# USB_CP2104.net
KiCad netlist of a schematic drawn in Altium Designer
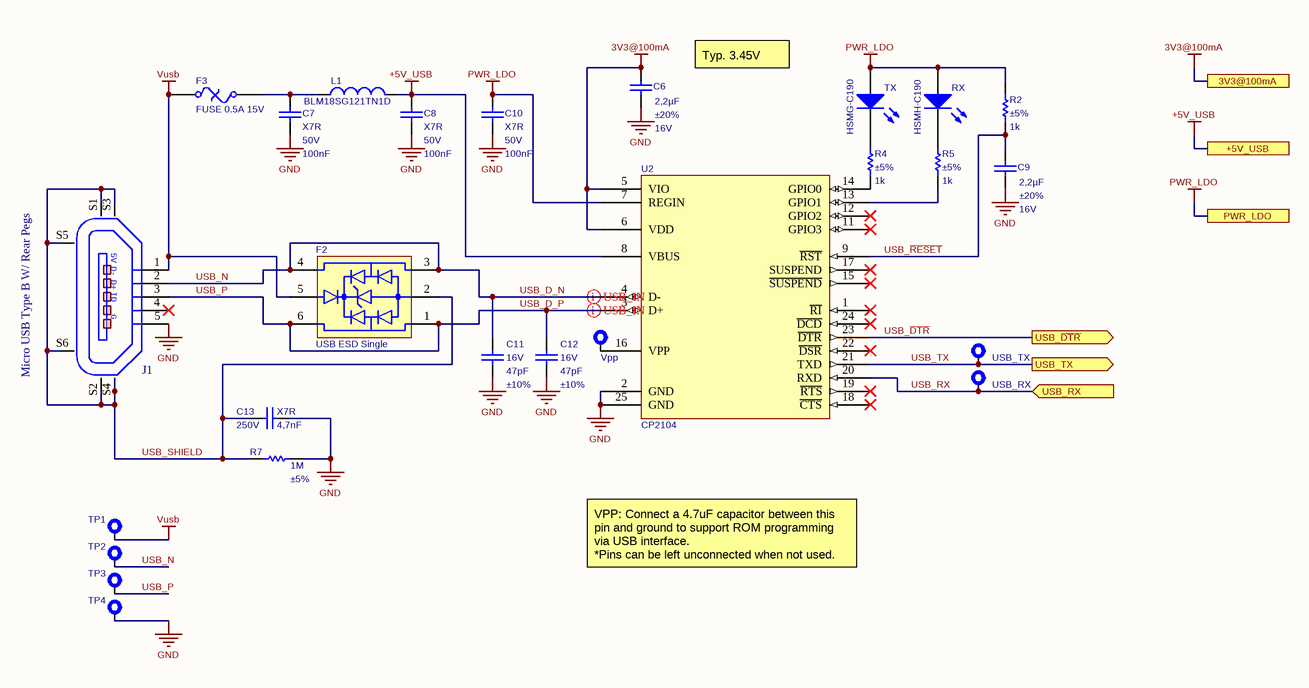
[diagram p0: USB_CP2104.SchDoc]

(export (version "E")
  (design (tool "Eeschema 10.0.6"))
  (components
    (comp (ref "C6")
      (value "C0402_2.2uF_16V_±20%")
      (footprint "C0402")
      (description "C0402_2.2uF_16V_±20%_X5R")
      (fields
        (field (name "VOLTAGE") "16V")
        (field (name "CAPACITANCE") "2,2µF")
        (field (name "PART NUMBER") "C0402_2.2uF_16V_±10%")
        (field (name "TOLERANCE") "±20%")
        (field (name "MANUFACTURER") "TDK")
      )
      (libsource (lib "BQ Vault") (part "Capacitor"))
    )
    (comp (ref "C7")
      (value "C0603_100nF_50V_±10%_X7R")
      (footprint "C0603")
      (fields
        (field (name "DIELECTRIC") "X7R")
        (field (name "VOLTAGE") "50V")
        (field (name "CAPACITANCE") "100nF")
        (field (name "MANUFACTURER") "Kemet")
        (field (name "TOLERANCE") "±10%")
      )
      (libsource (lib "BQ Vault") (part "CMP-00257-1"))
    )
    (comp (ref "C8")
      (value "C0603_100nF_50V_±10%_X7R")
      (footprint "C0603")
      (fields
        (field (name "DIELECTRIC") "X7R")
        (field (name "VOLTAGE") "50V")
        (field (name "CAPACITANCE") "100nF")
        (field (name "MANUFACTURER") "Kemet")
        (field (name "TOLERANCE") "±10%")
      )
      (libsource (lib "BQ Vault") (part "CMP-00257-1"))
    )
    (comp (ref "C9")
      (value "C0402_2.2uF_16V_±20%")
      (footprint "C0402")
      (description "C0402_2.2uF_16V_±20%_X5R")
      (fields
        (field (name "VOLTAGE") "16V")
        (field (name "CAPACITANCE") "2,2µF")
        (field (name "PART NUMBER") "C0402_2.2uF_16V_±10%")
        (field (name "TOLERANCE") "±20%")
        (field (name "MANUFACTURER") "TDK")
      )
      (libsource (lib "BQ Vault") (part "Capacitor"))
    )
    (comp (ref "C10")
      (value "C0603_100nF_50V_±10%_X7R")
      (footprint "C0603")
      (fields
        (field (name "DIELECTRIC") "X7R")
        (field (name "VOLTAGE") "50V")
        (field (name "CAPACITANCE") "100nF")
        (field (name "MANUFACTURER") "Kemet")
        (field (name "TOLERANCE") "±10%")
      )
      (libsource (lib "BQ Vault") (part "CMP-00257-1"))
    )
    (comp (ref "C11")
      (value "C0402_47pF_16V_±10%")
      (footprint "C0402")
      (fields
        (field (name "VOLTAGE") "16V")
        (field (name "CAPACITANCE") "47pF")
        (field (name "TOLERANCE") "±10%")
        (field (name "MANUFACTURER") "Kemet")
      )
      (libsource (lib "BQ Vault") (part "Capacitor"))
    )
    (comp (ref "C12")
      (value "C0402_47pF_16V_±10%")
      (footprint "C0402")
      (fields
        (field (name "VOLTAGE") "16V")
        (field (name "CAPACITANCE") "47pF")
        (field (name "TOLERANCE") "±10%")
        (field (name "MANUFACTURER") "Kemet")
      )
      (libsource (lib "BQ Vault") (part "Capacitor"))
    )
    (comp (ref "C13")
      (value "C0805_4700pF_250V_±10%_X7R")
      (footprint "C0805")
      (fields
        (field (name "DIELECTRIC") "X7R")
        (field (name "VOLTAGE") "250V")
        (field (name "CAPACITANCE") "4,7nF")
        (field (name "MANUFACTURER") "Kemet")
        (field (name "TOLERANCE") "±10%")
      )
      (libsource (lib "BQ Vault") (part "CMP-00357-1"))
    )
    (comp (ref "F2")
      (value "USB ESD Single")
      (footprint "SOT563")
      (description "TVS Diode Array")
      (fields (field (name "MANUFACTURER") "Würth Elektronik"))
      (libsource (lib "BQ Vault") (part "ESDUSB"))
    )
    (comp (ref "F3")
      (value "FUSE 0.5A 15V")
      (footprint "F1812")
      (description "Resettable Fuses")
      (fields (field (name "VOLTAGE") "15V") (field (name "MANUFACTURER") "Bourns"))
      (libsource (lib "BQ Vault") (part "PTC_Fuse"))
    )
    (comp (ref "J1")
      (value "Micro USB Type B W/ Rear Pegs")
      (footprint "USB_B_W_REAR_PEGS")
      (fields (field (name "MANUFACTURER") "FCI"))
      (libsource (lib "BQ Vault") (part "USB_Micro_Type_B"))
    )
    (comp (ref "L1")
      (value "L0603_120R_0,025R_3000mA")
      (footprint "L0603")
      (fields (field (name "ORDERINGCODE") "BLM18SG121TN1D") (field (name "MANUFACTURER") "Murata"))
      (libsource (lib "BQ Vault") (part "Ferrite Bead"))
    )
    (comp (ref "R2")
      (value "R0402_1k_0.063W_±5%")
      (footprint "R0402")
      (fields
        (field (name "TOLERANCE") "±5%")
        (field (name "POWER") "0.063W")
        (field (name "RESISTANCE") "1k")
        (field (name "MANUFACTURER") "Vishay")
      )
      (libsource (lib "BQ Vault") (part "Resistor"))
    )
    (comp (ref "R4")
      (value "R0402_1k_0.063W_±5%")
      (footprint "R0402")
      (fields
        (field (name "TOLERANCE") "±5%")
        (field (name "POWER") "0.063W")
        (field (name "RESISTANCE") "1k")
        (field (name "MANUFACTURER") "Vishay")
      )
      (libsource (lib "BQ Vault") (part "Resistor"))
    )
    (comp (ref "R5")
      (value "R0402_1k_0.063W_±5%")
      (footprint "R0402")
      (fields
        (field (name "TOLERANCE") "±5%")
        (field (name "POWER") "0.063W")
        (field (name "RESISTANCE") "1k")
        (field (name "MANUFACTURER") "Vishay")
      )
      (libsource (lib "BQ Vault") (part "Resistor"))
    )
    (comp (ref "R7")
      (value "R0603_1M_0.1W_±5%")
      (footprint "R0603")
      (fields
        (field (name "TOLERANCE") "±5%")
        (field (name "POWER") "0.1W")
        (field (name "RESISTANCE") "1M")
        (field (name "MANUFACTURER") "Vishay")
      )
      (libsource (lib "BQ Vault") (part "Resistor"))
    )
    (comp (ref "RX")
      (value "HSMH-C190")
      (footprint "LED0603")
      (description "LED")
      (fields (field (name "MANUFACTURER") "Avago Technologies"))
      (libsource (lib "BQ Vault") (part "LED"))
    )
    (comp (ref "TP1")
      (value "TP")
      (footprint "TP_POWER")
      (description "Testpoint 0.3mm")
      (fields (field (name "MANUFACTURER") "Oxley") (field (name "PART NUMBER") "TP_POWER"))
      (libsource (lib "BQ Vault") (part "CMP-A2499-3"))
    )
    (comp (ref "TP2")
      (value "TP_POWER")
      (footprint "TP_POWER")
      (description "Testpoint 0.3mm")
      (fields (field (name "MANUFACTURER") "Oxley"))
      (libsource (lib "BQ Vault") (part "CMP-A2499-3"))
    )
    (comp (ref "TP3")
      (value "TP_POWER")
      (footprint "TP_POWER")
      (description "Testpoint 0.3mm")
      (fields (field (name "MANUFACTURER") "Oxley"))
      (libsource (lib "BQ Vault") (part "CMP-A2499-3"))
    )
    (comp (ref "TP4")
      (value "TP_POWER")
      (footprint "TP_POWER")
      (description "Testpoint 0.3mm")
      (fields (field (name "MANUFACTURER") "Oxley"))
      (libsource (lib "BQ Vault") (part "CMP-A2499-3"))
    )
    (comp (ref "TX")
      (value "HSMG-C190")
      (footprint "LED0603")
      (description "LED")
      (fields (field (name "MANUFACTURER") "Avago Technologies"))
      (libsource (lib "BQ Vault") (part "LED"))
    )
    (comp (ref "U2")
      (value "CP2104")
      (footprint "QFN24_no_power")
      (description "USB to UART Bridge")
      (fields (field (name "MANUFACTURER") "Silicon Labs"))
      (libsource (lib "BQ Vault") (part "CP2104"))
    )
    (comp (ref "USB_RX")
      (value "TP_POWER")
      (footprint "TP_POWER")
      (description "Testpoint 0.3mm")
      (fields (field (name "MANUFACTURER") "Oxley"))
      (libsource (lib "BQ Vault") (part "CMP-A2499-3"))
    )
    (comp (ref "USB_TX")
      (value "TP_POWER")
      (footprint "TP_POWER")
      (description "Testpoint 0.3mm")
      (fields (field (name "MANUFACTURER") "Oxley"))
      (libsource (lib "BQ Vault") (part "CMP-A2499-3"))
    )
    (comp (ref "Vpp")
      (value "TP_POWER")
      (footprint "TP_POWER")
      (description "Testpoint 0.3mm")
      (fields (field (name "MANUFACTURER") "Oxley"))
      (libsource (lib "BQ Vault") (part "CMP-A2499-3"))
    )
  )
  (nets
    (net (code "1") (name "+5V_USB") (class "Default")
      (node (ref "C8") (pin "2") (pinfunction "2_2") (pintype "passive"))
      (node (ref "L1") (pin "2") (pinfunction "2_2") (pintype "passive"))
      (node (ref "U2") (pin "8") (pinfunction "VBUS_8") (pintype "power_in"))
    )
    (net (code "2") (name "/USB_D_N") (class "Default")
      (node (ref "C11") (pin "2") (pinfunction "2_2") (pintype "passive"))
      (node (ref "F2") (pin "3") (pinfunction "3_3") (pintype "passive"))
      (node (ref "F2") (pin "4") (pinfunction "4_4") (pintype "passive"))
      (node (ref "J1") (pin "2") (pinfunction "P2_2") (pintype "passive"))
      (node (ref "TP2") (pin "1") (pinfunction "1_1") (pintype "passive"))
      (node (ref "U2") (pin "4") (pinfunction "D-_4") (pintype "bidirectional"))
    )
    (net (code "3") (name "/USB_D_P") (class "Default")
      (node (ref "C12") (pin "2") (pinfunction "2_2") (pintype "passive"))
      (node (ref "F2") (pin "1") (pinfunction "1_1") (pintype "passive"))
      (node (ref "F2") (pin "6") (pinfunction "6_6") (pintype "passive"))
      (node (ref "J1") (pin "3") (pinfunction "P3_3") (pintype "passive"))
      (node (ref "TP3") (pin "1") (pinfunction "1_1") (pintype "passive"))
      (node (ref "U2") (pin "3") (pinfunction "D+_3") (pintype "bidirectional"))
    )
    (net (code "4") (name "/USB_RX") (class "Default")
      (node (ref "U2") (pin "20") (pinfunction "RXD_20") (pintype "input"))
      (node (ref "USB_RX") (pin "1") (pinfunction "1_1") (pintype "passive"))
    )
    (net (code "5") (name "/USB_SHIELD") (class "Default")
      (node (ref "C13") (pin "1") (pinfunction "1_1") (pintype "passive"))
      (node (ref "F2") (pin "2") (pinfunction "2_2") (pintype "passive"))
      (node (ref "J1") (pin "S1") (pinfunction "SHLD1_S1") (pintype "passive"))
      (node (ref "J1") (pin "S2") (pinfunction "SHLD2_S2") (pintype "passive"))
      (node (ref "J1") (pin "S3") (pinfunction "SHLD3_S3") (pintype "passive"))
      (node (ref "J1") (pin "S4") (pinfunction "SHLD4_S4") (pintype "passive"))
      (node (ref "J1") (pin "S5") (pinfunction "SHLD5_S5") (pintype "passive"))
      (node (ref "J1") (pin "S6") (pinfunction "SHLD6_S6") (pintype "passive"))
      (node (ref "R7") (pin "2") (pinfunction "2_2") (pintype "passive"))
    )
    (net (code "6") (name "/USB_TX") (class "Default")
      (node (ref "U2") (pin "21") (pinfunction "TXD_21") (pintype "output"))
      (node (ref "USB_TX") (pin "1") (pinfunction "1_1") (pintype "passive"))
    )
    (net (code "7") (name "/USB_~{DTR}") (class "Default")
      (node (ref "U2") (pin "23") (pinfunction "~{DTR}_23") (pintype "output"))
    )
    (net (code "8") (name "/USB_~{RESET}") (class "Default")
      (node (ref "C9") (pin "2") (pinfunction "2_2") (pintype "passive"))
      (node (ref "R2") (pin "1") (pinfunction "1_1") (pintype "passive"))
      (node (ref "U2") (pin "9") (pinfunction "~{RST}_9") (pintype "input"))
    )
    (net (code "9") (name "3V3@100mA") (class "Default")
      (node (ref "C6") (pin "2") (pinfunction "2_2") (pintype "passive"))
      (node (ref "U2") (pin "5") (pinfunction "VIO_5") (pintype "power_in"))
      (node (ref "U2") (pin "6") (pinfunction "VDD_6") (pintype "power_in"))
    )
    (net (code "10") (name "GND") (class "Default")
      (node (ref "C10") (pin "1") (pinfunction "1_1") (pintype "passive"))
      (node (ref "C11") (pin "1") (pinfunction "1_1") (pintype "passive"))
      (node (ref "C12") (pin "1") (pinfunction "1_1") (pintype "passive"))
      (node (ref "C13") (pin "2") (pinfunction "2_2") (pintype "passive"))
      (node (ref "C6") (pin "1") (pinfunction "1_1") (pintype "passive"))
      (node (ref "C7") (pin "1") (pinfunction "1_1") (pintype "passive"))
      (node (ref "C8") (pin "1") (pinfunction "1_1") (pintype "passive"))
      (node (ref "C9") (pin "1") (pinfunction "1_1") (pintype "passive"))
      (node (ref "J1") (pin "5") (pinfunction "P5_5") (pintype "passive"))
      (node (ref "R7") (pin "1") (pinfunction "1_1") (pintype "passive"))
      (node (ref "TP4") (pin "1") (pinfunction "1_1") (pintype "passive"))
      (node (ref "U2") (pin "2") (pinfunction "GND_2") (pintype "power_in"))
      (node (ref "U2") (pin "25") (pinfunction "GND_25") (pintype "power_in"))
    )
    (net (code "11") (name "Net-(C7-Pad2)") (class "Default")
      (node (ref "C7") (pin "2") (pinfunction "2_2") (pintype "passive"))
      (node (ref "F3") (pin "2") (pinfunction "2_2") (pintype "passive"))
      (node (ref "L1") (pin "1") (pinfunction "1_1") (pintype "passive"))
    )
    (net (code "12") (name "Net-(R4-Pad2)") (class "Default")
      (node (ref "R4") (pin "2") (pinfunction "2_2") (pintype "passive"))
      (node (ref "TX") (pin "K") (pinfunction "K_K") (pintype "passive"))
    )
    (net (code "13") (name "Net-(R5-Pad2)") (class "Default")
      (node (ref "R5") (pin "2") (pinfunction "2_2") (pintype "passive"))
      (node (ref "RX") (pin "K") (pinfunction "K_K") (pintype "passive"))
    )
    (net (code "14") (name "Net-(U2-GPIO0)") (class "Default")
      (node (ref "R4") (pin "1") (pinfunction "1_1") (pintype "passive"))
      (node (ref "U2") (pin "14") (pinfunction "GPIO0_14") (pintype "bidirectional"))
    )
    (net (code "15") (name "Net-(U2-GPIO1)") (class "Default")
      (node (ref "R5") (pin "1") (pinfunction "1_1") (pintype "passive"))
      (node (ref "U2") (pin "13") (pinfunction "GPIO1_13") (pintype "bidirectional"))
    )
    (net (code "16") (name "Net-(U2-VPP)") (class "Default")
      (node (ref "U2") (pin "16") (pinfunction "VPP_16") (pintype "power_in"))
      (node (ref "Vpp") (pin "1") (pinfunction "1_1") (pintype "passive"))
    )
    (net (code "17") (name "PWR_LDO") (class "Default")
      (node (ref "C10") (pin "2") (pinfunction "2_2") (pintype "passive"))
      (node (ref "R2") (pin "2") (pinfunction "2_2") (pintype "passive"))
      (node (ref "RX") (pin "A") (pinfunction "A_A") (pintype "passive"))
      (node (ref "TX") (pin "A") (pinfunction "A_A") (pintype "passive"))
      (node (ref "U2") (pin "7") (pinfunction "REGIN_7") (pintype "power_in"))
    )
    (net (code "18") (name "Vusb") (class "Default")
      (node (ref "F2") (pin "5") (pinfunction "5_5") (pintype "passive"))
      (node (ref "F3") (pin "1") (pinfunction "1_1") (pintype "passive"))
      (node (ref "J1") (pin "1") (pinfunction "P1_1") (pintype "passive"))
      (node (ref "TP1") (pin "1") (pinfunction "1_1") (pintype "passive"))
    )
    (net (code "19") (name "unconnected-(J1-P4-Pad4)") (class "Default")
      (node (ref "J1") (pin "4") (pinfunction "P4_4") (pintype "passive+no_connect"))
    )
    (net (code "20") (name "unconnected-(U2-GPIO2-Pad12)") (class "Default")
      (node (ref "U2") (pin "12") (pinfunction "GPIO2_12") (pintype "bidirectional+no_connect"))
    )
    (net (code "21") (name "unconnected-(U2-GPIO3-Pad11)") (class "Default")
      (node (ref "U2") (pin "11") (pinfunction "GPIO3_11") (pintype "bidirectional+no_connect"))
    )
    (net (code "22") (name "unconnected-(U2-SUSPEND-Pad17)") (class "Default")
      (node (ref "U2") (pin "17") (pinfunction "SUSPEND_17") (pintype "output+no_connect"))
    )
    (net (code "23") (name "unconnected-(U2-~{CTS}-Pad18)") (class "Default")
      (node (ref "U2") (pin "18") (pinfunction "~{CTS}_18") (pintype "input+no_connect"))
    )
    (net (code "24") (name "unconnected-(U2-~{DCD}-Pad24)") (class "Default")
      (node (ref "U2") (pin "24") (pinfunction "~{DCD}_24") (pintype "input+no_connect"))
    )
    (net (code "25") (name "unconnected-(U2-~{DSR}-Pad22)") (class "Default")
      (node (ref "U2") (pin "22") (pinfunction "~{DSR}_22") (pintype "input+no_connect"))
    )
    (net (code "26") (name "unconnected-(U2-~{RI}-Pad1)") (class "Default")
      (node (ref "U2") (pin "1") (pinfunction "~{RI}_1") (pintype "input+no_connect"))
    )
    (net (code "27") (name "unconnected-(U2-~{RTS}-Pad19)") (class "Default")
      (node (ref "U2") (pin "19") (pinfunction "~{RTS}_19") (pintype "output+no_connect"))
    )
    (net (code "28") (name "unconnected-(U2-~{SUSPEND}-Pad15)") (class "Default")
      (node (ref "U2") (pin "15") (pinfunction "~{SUSPEND}_15") (pintype "output+no_connect"))
    )
  )
)
